# master_jorge3.net
KiCad netlist of a schematic drawn in EAGLE
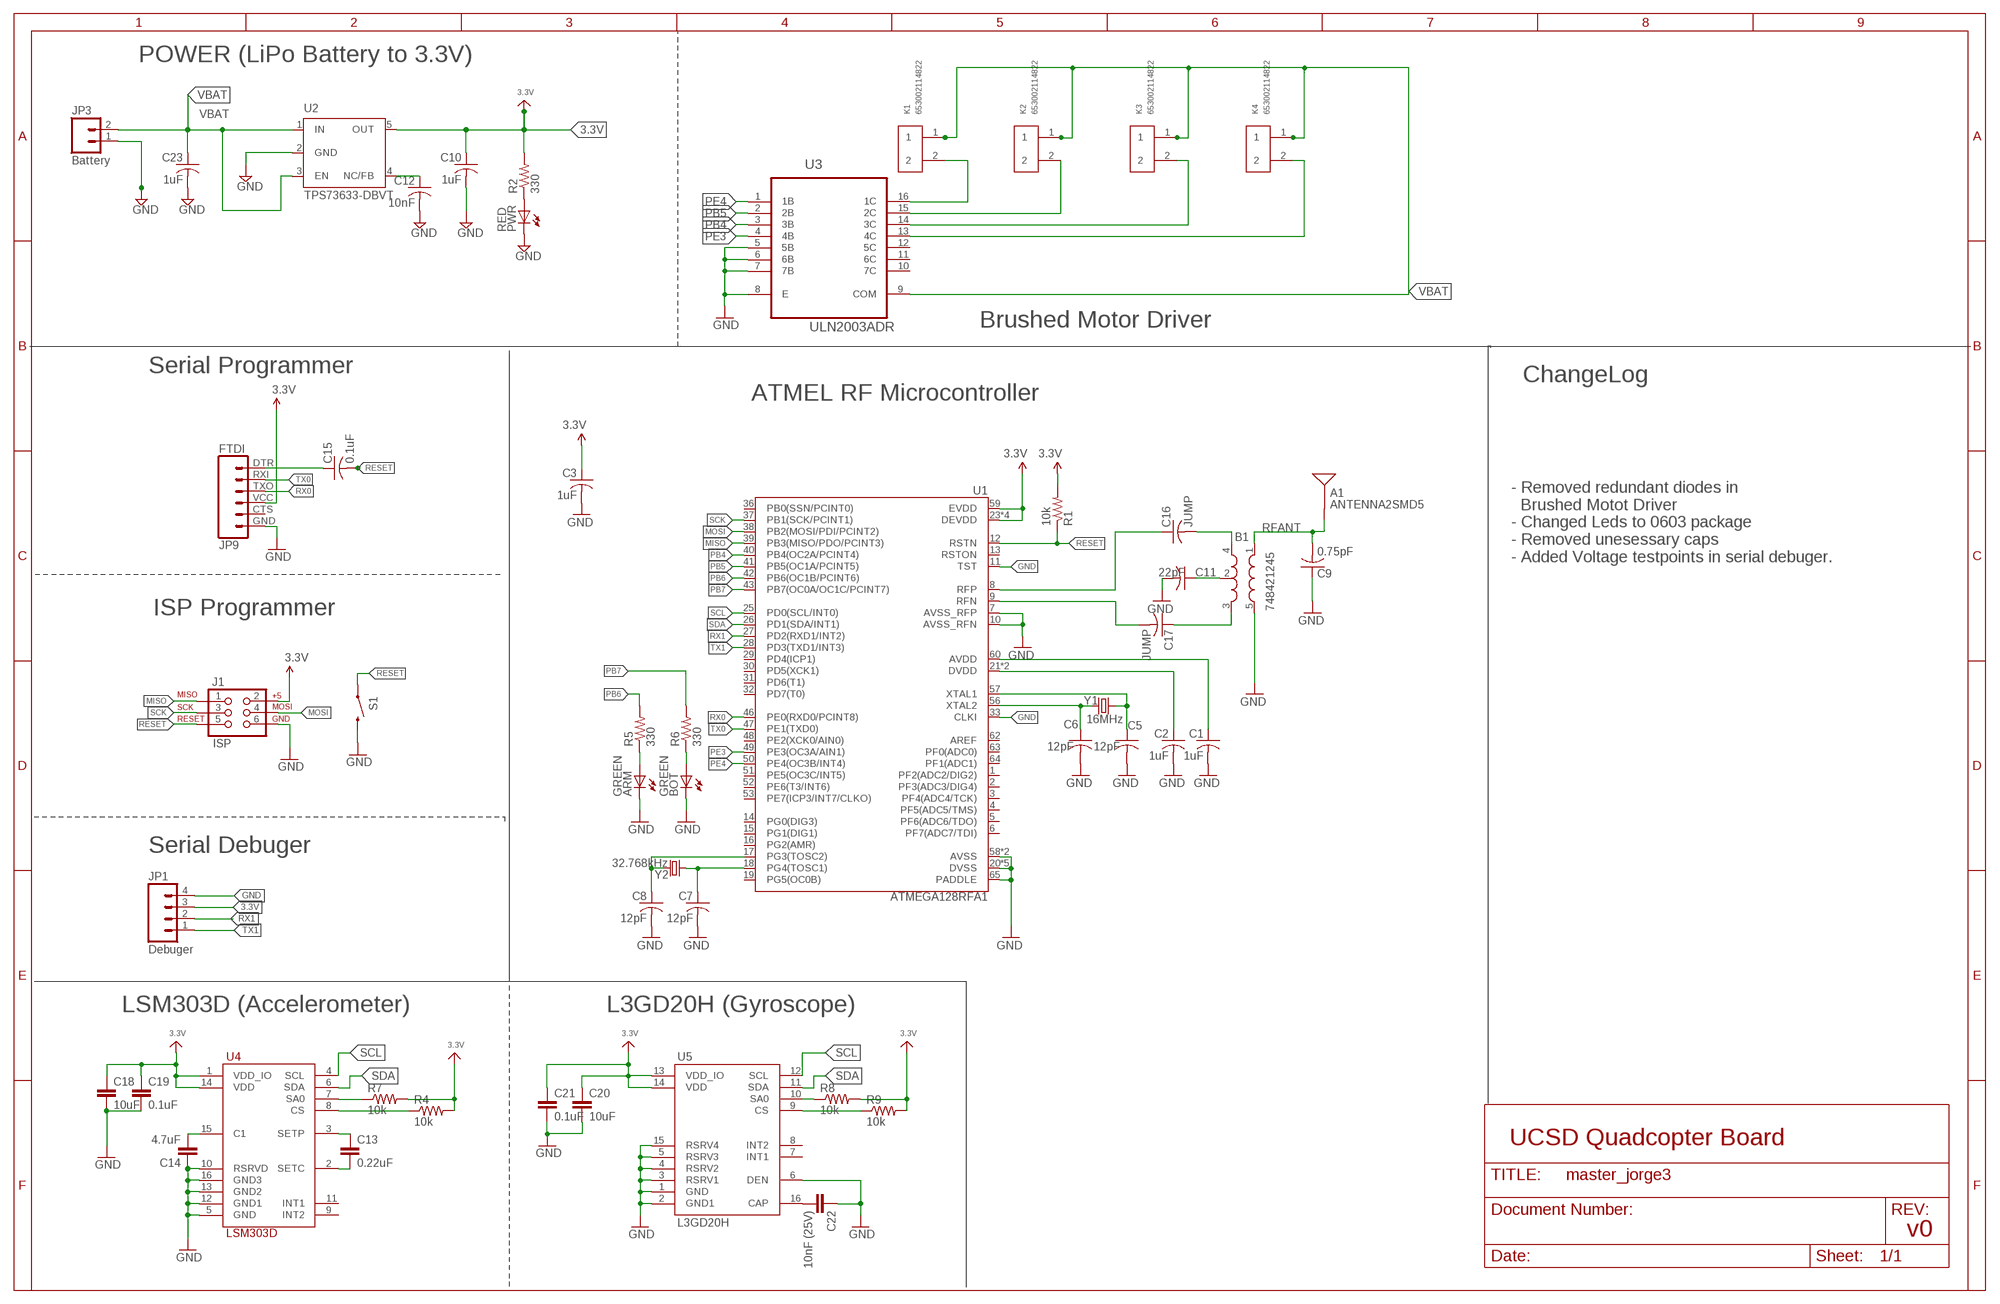
[diagram p0: schematic, sheet 1]

(export (version "E")
  (design (tool "Eeschema 10.0.6"))
  (components
    (comp (ref "A1")
      (value "ANTENNA2SMD5")
      (footprint "eagle-import:ANTENNA-CHIP5")
      (libsource (lib "eagle-import") (part "ANTENNA2SMD5"))
    )
    (comp (ref "ARM")
      (value "GREEN")
      (footprint "eagle-import:CHIPLED_0603")
      (libsource (lib "eagle-import") (part "LEDCHIPLED_0603"))
    )
    (comp (ref "B1")
      (value "748421245")
      (footprint "eagle-import:BALUN")
      (libsource (lib "eagle-import") (part "BALUN0805"))
    )
    (comp (ref "BOT")
      (value "GREEN")
      (footprint "eagle-import:CHIPLED_0603")
      (libsource (lib "eagle-import") (part "LEDCHIPLED_0603"))
    )
    (comp (ref "C1")
      (value "1uF")
      (footprint "eagle-import:C0805")
      (libsource (lib "eagle-import") (part "C-USC0805"))
    )
    (comp (ref "C2")
      (value "1uF")
      (footprint "eagle-import:C0805")
      (libsource (lib "eagle-import") (part "C-USC0805"))
    )
    (comp (ref "C3")
      (value "1uF")
      (footprint "eagle-import:C0805")
      (libsource (lib "eagle-import") (part "C-USC0805"))
    )
    (comp (ref "C5")
      (value "12pF")
      (footprint "eagle-import:C0805")
      (libsource (lib "eagle-import") (part "C-USC0805"))
    )
    (comp (ref "C6")
      (value "12pF")
      (footprint "eagle-import:C0805")
      (libsource (lib "eagle-import") (part "C-USC0805"))
    )
    (comp (ref "C7")
      (value "12pF")
      (footprint "eagle-import:C0805")
      (libsource (lib "eagle-import") (part "C-USC0805"))
    )
    (comp (ref "C8")
      (value "12pF")
      (footprint "eagle-import:C0805")
      (libsource (lib "eagle-import") (part "C-USC0805"))
    )
    (comp (ref "C9")
      (value "0.75pF")
      (footprint "eagle-import:C0805")
      (libsource (lib "eagle-import") (part "C-USC0805"))
    )
    (comp (ref "C10")
      (value "1uF")
      (footprint "eagle-import:C0805")
      (libsource (lib "eagle-import") (part "C-USC0805"))
    )
    (comp (ref "C11")
      (value "22pF")
      (footprint "eagle-import:C0805")
      (libsource (lib "eagle-import") (part "C-USC0805"))
    )
    (comp (ref "C12")
      (value "10nF")
      (footprint "eagle-import:C0805")
      (libsource (lib "eagle-import") (part "C-USC0805"))
    )
    (comp (ref "C13")
      (value "0.22uF")
      (footprint "eagle-import:0805")
      (libsource (lib "eagle-import") (part "CAP0805"))
    )
    (comp (ref "C14")
      (value "4.7uF")
      (footprint "eagle-import:0805")
      (libsource (lib "eagle-import") (part "CAP0805"))
    )
    (comp (ref "C15")
      (value "0.1uF")
      (footprint "eagle-import:C0805")
      (libsource (lib "eagle-import") (part "C-USC0805"))
    )
    (comp (ref "C16")
      (value "JUMP")
      (footprint "eagle-import:C0805")
      (libsource (lib "eagle-import") (part "C-USC0805"))
    )
    (comp (ref "C17")
      (value "JUMP")
      (footprint "eagle-import:C0805")
      (libsource (lib "eagle-import") (part "C-USC0805"))
    )
    (comp (ref "C18")
      (value "10uF")
      (footprint "eagle-import:0805")
      (libsource (lib "eagle-import") (part "CAP0805"))
    )
    (comp (ref "C19")
      (value "0.1uF")
      (footprint "eagle-import:0805")
      (libsource (lib "eagle-import") (part "CAP0805"))
    )
    (comp (ref "C20")
      (value "10uF")
      (footprint "eagle-import:0805")
      (libsource (lib "eagle-import") (part "CAP0805"))
    )
    (comp (ref "C21")
      (value "0.1uF")
      (footprint "eagle-import:0805")
      (libsource (lib "eagle-import") (part "CAP0805"))
    )
    (comp (ref "C22")
      (value "10nF (25V)")
      (footprint "eagle-import:0805")
      (libsource (lib "eagle-import") (part "CAP0805"))
    )
    (comp (ref "C23")
      (value "1uF")
      (footprint "eagle-import:C0805")
      (libsource (lib "eagle-import") (part "C-USC0805"))
    )
    (comp (ref "J1")
      (value "ISP")
      (footprint "eagle-import:2X3-NS")
      (libsource (lib "eagle-import") (part "AVR_SPI_PRG_6NS"))
    )
    (comp (ref "JP1")
      (value "Debuger")
      (footprint "eagle-import:1X04")
      (libsource (lib "eagle-import") (part "M04PTH"))
    )
    (comp (ref "JP3")
      (value "Battery")
      (footprint "eagle-import:1X02")
      (libsource (lib "eagle-import") (part "M02PTH"))
    )
    (comp (ref "JP9")
      (value "FTDI")
      (footprint "eagle-import:FTDI_BASIC")
      (libsource (lib "eagle-import") (part "FTDI_BASICPTH"))
    )
    (comp (ref "K1")
      (value "653002114822")
      (footprint "eagle-import:653002114822")
      (libsource (lib "eagle-import") (part "653002114822"))
    )
    (comp (ref "K2")
      (value "653002114822")
      (footprint "eagle-import:653002114822")
      (libsource (lib "eagle-import") (part "653002114822"))
    )
    (comp (ref "K3")
      (value "653002114822")
      (footprint "eagle-import:653002114822")
      (libsource (lib "eagle-import") (part "653002114822"))
    )
    (comp (ref "K4")
      (value "653002114822")
      (footprint "eagle-import:653002114822")
      (libsource (lib "eagle-import") (part "653002114822"))
    )
    (comp (ref "PWR")
      (value "RED")
      (footprint "eagle-import:CHIPLED_0603")
      (libsource (lib "eagle-import") (part "LEDCHIPLED_0603"))
    )
    (comp (ref "R1")
      (value "10k")
      (footprint "eagle-import:R0805")
      (libsource (lib "eagle-import") (part "R-US_R0805"))
    )
    (comp (ref "R2")
      (value "330")
      (footprint "eagle-import:R0805")
      (libsource (lib "eagle-import") (part "R-US_R0805"))
    )
    (comp (ref "R4")
      (value "10k")
      (footprint "eagle-import:0805")
      (libsource (lib "eagle-import") (part "RESISTOR0805-RES"))
    )
    (comp (ref "R5")
      (value "330")
      (footprint "eagle-import:R0805")
      (libsource (lib "eagle-import") (part "R-US_R0805"))
    )
    (comp (ref "R6")
      (value "330")
      (footprint "eagle-import:R0805")
      (libsource (lib "eagle-import") (part "R-US_R0805"))
    )
    (comp (ref "R7")
      (value "10k")
      (footprint "eagle-import:0805")
      (libsource (lib "eagle-import") (part "RESISTOR0805-RES"))
    )
    (comp (ref "R8")
      (value "10k")
      (footprint "eagle-import:0805")
      (libsource (lib "eagle-import") (part "RESISTOR0805-RES"))
    )
    (comp (ref "R9")
      (value "10k")
      (footprint "eagle-import:0805")
      (libsource (lib "eagle-import") (part "RESISTOR0805-RES"))
    )
    (comp (ref "S1")
      (value "SWITCH-MOMENTARY-2SMD")
      (footprint "eagle-import:TACTILE_SWITCH_SMD")
      (libsource (lib "eagle-import") (part "SWITCH-MOMENTARY-2SMD"))
    )
    (comp (ref "U1")
      (value "ATMEGA128RFA1")
      (footprint "eagle-import:QFN-64")
      (libsource (lib "eagle-import") (part "ATMEGA128RFA1"))
    )
    (comp (ref "U2")
      (value "TPS73633-DBVT")
      (footprint "eagle-import:SOT23-DBV")
      (libsource (lib "eagle-import") (part "TPS73633-DBVT"))
    )
    (comp (ref "U3")
      (value "ULN2003ADR")
      (footprint "eagle-import:SOIC127P600X175-16N")
      (libsource (lib "eagle-import") (part "ULN2003ADR"))
    )
    (comp (ref "U4")
      (value "LSM303D")
      (footprint "eagle-import:LGA16_3X3MM")
      (libsource (lib "eagle-import") (part "LSM303D"))
    )
    (comp (ref "U5")
      (value "L3GD20H")
      (footprint "eagle-import:LGA16_3X3MM")
      (libsource (lib "eagle-import") (part "L3GD20H"))
    )
    (comp (ref "Y1")
      (value "16MHz")
      (footprint "eagle-import:CRYSTAL-SMD-5X3")
      (libsource (lib "eagle-import") (part "CRYSTAL5X3"))
    )
    (comp (ref "Y2")
      (value "32.768kHz")
      (footprint "eagle-import:CRYSTAL-32KHZ-SMD")
      (libsource (lib "eagle-import") (part "CRYSTAL32-SMD"))
    )
  )
  (nets
    (net (code "1") (name "/RFANT") (class "Default")
      (node (ref "A1") (pin "FEED") (pinfunction "SIGNAL_FEED") (pintype "bidirectional"))
      (node (ref "B1") (pin "1") (pinfunction "IN_1") (pintype "bidirectional"))
      (node (ref "C9") (pin "2") (pinfunction "2_2") (pintype "passive"))
    )
    (net (code "2") (name "3.3V") (class "Default")
      (node (ref "C10") (pin "1") (pinfunction "1_1") (pintype "passive"))
      (node (ref "C18") (pin "1") (pinfunction "1_1") (pintype "passive"))
      (node (ref "C19") (pin "1") (pinfunction "1_1") (pintype "passive"))
      (node (ref "C20") (pin "1") (pinfunction "1_1") (pintype "passive"))
      (node (ref "C21") (pin "1") (pinfunction "1_1") (pintype "passive"))
      (node (ref "C3") (pin "1") (pinfunction "1_1") (pintype "passive"))
      (node (ref "J1") (pin "2") (pinfunction "2_2") (pintype "passive"))
      (node (ref "JP1") (pin "3") (pinfunction "3_3") (pintype "passive"))
      (node (ref "JP9") (pin "VCC") (pinfunction "4_VCC") (pintype "passive"))
      (node (ref "R1") (pin "2") (pinfunction "2_2") (pintype "passive"))
      (node (ref "R2") (pin "2") (pinfunction "2_2") (pintype "passive"))
      (node (ref "R4") (pin "2") (pinfunction "2_2") (pintype "passive"))
      (node (ref "R7") (pin "2") (pinfunction "2_2") (pintype "passive"))
      (node (ref "R8") (pin "2") (pinfunction "2_2") (pintype "passive"))
      (node (ref "R9") (pin "2") (pinfunction "2_2") (pintype "passive"))
      (node (ref "U1") (pin "23") (pinfunction "DEVDD_23") (pintype "bidirectional"))
      (node (ref "U1") (pin "34") (pinfunction "DEVDD_34") (pintype "bidirectional"))
      (node (ref "U1") (pin "44") (pinfunction "DEVDD_44") (pintype "bidirectional"))
      (node (ref "U1") (pin "54") (pinfunction "DEVDD_54") (pintype "bidirectional"))
      (node (ref "U1") (pin "59") (pinfunction "EVDD_59") (pintype "bidirectional"))
      (node (ref "U2") (pin "5") (pinfunction "OUT_5") (pintype "passive"))
      (node (ref "U4") (pin "1") (pinfunction "VDD_IO_1") (pintype "bidirectional"))
      (node (ref "U4") (pin "14") (pinfunction "VDD_14") (pintype "bidirectional"))
      (node (ref "U5") (pin "13") (pinfunction "VDD_IO_13") (pintype "bidirectional"))
      (node (ref "U5") (pin "14") (pinfunction "VDD_14") (pintype "bidirectional"))
    )
    (net (code "3") (name "GND") (class "Default")
      (node (ref "ARM") (pin "C") (pinfunction "C_C") (pintype "passive"))
      (node (ref "B1") (pin "5") (pinfunction "GND_5") (pintype "bidirectional"))
      (node (ref "BOT") (pin "C") (pinfunction "C_C") (pintype "passive"))
      (node (ref "C1") (pin "2") (pinfunction "2_2") (pintype "passive"))
      (node (ref "C10") (pin "2") (pinfunction "2_2") (pintype "passive"))
      (node (ref "C11") (pin "2") (pinfunction "2_2") (pintype "passive"))
      (node (ref "C12") (pin "2") (pinfunction "2_2") (pintype "passive"))
      (node (ref "C14") (pin "1") (pinfunction "1_1") (pintype "passive"))
      (node (ref "C18") (pin "2") (pinfunction "2_2") (pintype "passive"))
      (node (ref "C19") (pin "2") (pinfunction "2_2") (pintype "passive"))
      (node (ref "C2") (pin "2") (pinfunction "2_2") (pintype "passive"))
      (node (ref "C20") (pin "2") (pinfunction "2_2") (pintype "passive"))
      (node (ref "C21") (pin "2") (pinfunction "2_2") (pintype "passive"))
      (node (ref "C22") (pin "1") (pinfunction "1_1") (pintype "passive"))
      (node (ref "C23") (pin "2") (pinfunction "2_2") (pintype "passive"))
      (node (ref "C3") (pin "2") (pinfunction "2_2") (pintype "passive"))
      (node (ref "C5") (pin "2") (pinfunction "2_2") (pintype "passive"))
      (node (ref "C6") (pin "2") (pinfunction "2_2") (pintype "passive"))
      (node (ref "C7") (pin "2") (pinfunction "2_2") (pintype "passive"))
      (node (ref "C8") (pin "2") (pinfunction "2_2") (pintype "passive"))
      (node (ref "C9") (pin "1") (pinfunction "1_1") (pintype "passive"))
      (node (ref "J1") (pin "6") (pinfunction "6_6") (pintype "passive"))
      (node (ref "JP1") (pin "4") (pinfunction "4_4") (pintype "passive"))
      (node (ref "JP3") (pin "1") (pinfunction "1_1") (pintype "passive"))
      (node (ref "JP9") (pin "GND") (pinfunction "6_GND") (pintype "passive"))
      (node (ref "PWR") (pin "C") (pinfunction "C_C") (pintype "passive"))
      (node (ref "S1") (pin "3") (pinfunction "2_3") (pintype "passive"))
      (node (ref "U1") (pin "10") (pinfunction "AVSS_RFN_10") (pintype "bidirectional"))
      (node (ref "U1") (pin "11") (pinfunction "TST_11") (pintype "bidirectional"))
      (node (ref "U1") (pin "20") (pinfunction "DVSS_20") (pintype "bidirectional"))
      (node (ref "U1") (pin "24") (pinfunction "DVSS_24") (pintype "bidirectional"))
      (node (ref "U1") (pin "33") (pinfunction "CLKI_33") (pintype "bidirectional"))
      (node (ref "U1") (pin "35") (pinfunction "DVSS_35") (pintype "bidirectional"))
      (node (ref "U1") (pin "45") (pinfunction "DVSS_45") (pintype "bidirectional"))
      (node (ref "U1") (pin "55") (pinfunction "DVSS_55") (pintype "bidirectional"))
      (node (ref "U1") (pin "58") (pinfunction "AVSS_58") (pintype "bidirectional"))
      (node (ref "U1") (pin "61") (pinfunction "AVSS_61") (pintype "bidirectional"))
      (node (ref "U1") (pin "65") (pinfunction "PADDLE_65") (pintype "bidirectional"))
      (node (ref "U1") (pin "7") (pinfunction "AVSS_RFP_7") (pintype "bidirectional"))
      (node (ref "U2") (pin "2") (pinfunction "GND_2") (pintype "input"))
      (node (ref "U3") (pin "5") (pinfunction "5B_5") (pintype "input"))
      (node (ref "U3") (pin "6") (pinfunction "6B_6") (pintype "input"))
      (node (ref "U3") (pin "7") (pinfunction "7B_7") (pintype "input"))
      (node (ref "U3") (pin "8") (pinfunction "E_8") (pintype "input"))
      (node (ref "U4") (pin "10") (pinfunction "RSRVD_10") (pintype "bidirectional"))
      (node (ref "U4") (pin "12") (pinfunction "GND1_12") (pintype "bidirectional"))
      (node (ref "U4") (pin "13") (pinfunction "GND2_13") (pintype "bidirectional"))
      (node (ref "U4") (pin "16") (pinfunction "GND3_16") (pintype "bidirectional"))
      (node (ref "U4") (pin "5") (pinfunction "GND_5") (pintype "bidirectional"))
      (node (ref "U5") (pin "1") (pinfunction "GND_1") (pintype "bidirectional"))
      (node (ref "U5") (pin "15") (pinfunction "RSRV4_15") (pintype "bidirectional"))
      (node (ref "U5") (pin "2") (pinfunction "GND1_2") (pintype "bidirectional"))
      (node (ref "U5") (pin "3") (pinfunction "RSRV1_3") (pintype "bidirectional"))
      (node (ref "U5") (pin "4") (pinfunction "RSRV2_4") (pintype "bidirectional"))
      (node (ref "U5") (pin "5") (pinfunction "RSRV3_5") (pintype "bidirectional"))
      (node (ref "U5") (pin "6") (pinfunction "DEN_6") (pintype "bidirectional"))
    )
    (net (code "4") (name "MISO") (class "Default")
      (node (ref "J1") (pin "1") (pinfunction "1_1") (pintype "passive"))
      (node (ref "U1") (pin "39") (pinfunction "PB3(MISO/PDO/PCINT3)_39") (pintype "bidirectional"))
    )
    (net (code "5") (name "MOSI") (class "Default")
      (node (ref "J1") (pin "4") (pinfunction "4_4") (pintype "passive"))
      (node (ref "U1") (pin "38") (pinfunction "PB2(MOSI/PDI/PCINT2)_38") (pintype "bidirectional"))
    )
    (net (code "6") (name "Net-(ARM-PadA)") (class "Default")
      (node (ref "ARM") (pin "A") (pinfunction "A_A") (pintype "passive"))
      (node (ref "R5") (pin "1") (pinfunction "1_1") (pintype "passive"))
    )
    (net (code "7") (name "Net-(B1-GND-Pad2)") (class "Default")
      (node (ref "B1") (pin "2") (pinfunction "GND_2") (pintype "bidirectional"))
      (node (ref "C11") (pin "1") (pinfunction "1_1") (pintype "passive"))
    )
    (net (code "8") (name "Net-(B1-OUT1)") (class "Default")
      (node (ref "B1") (pin "4") (pinfunction "OUT1_4") (pintype "bidirectional"))
      (node (ref "C16") (pin "2") (pinfunction "2_2") (pintype "passive"))
    )
    (net (code "9") (name "Net-(B1-OUT2)") (class "Default")
      (node (ref "B1") (pin "3") (pinfunction "OUT2_3") (pintype "bidirectional"))
      (node (ref "C17") (pin "1") (pinfunction "1_1") (pintype "passive"))
    )
    (net (code "10") (name "Net-(BOT-PadA)") (class "Default")
      (node (ref "BOT") (pin "A") (pinfunction "A_A") (pintype "passive"))
      (node (ref "R6") (pin "1") (pinfunction "1_1") (pintype "passive"))
    )
    (net (code "11") (name "Net-(C2-Pad1)") (class "Default")
      (node (ref "C2") (pin "1") (pinfunction "1_1") (pintype "passive"))
      (node (ref "U1") (pin "21") (pinfunction "DVDD_21") (pintype "bidirectional"))
      (node (ref "U1") (pin "22") (pinfunction "DVDD_22") (pintype "bidirectional"))
    )
    (net (code "12") (name "Net-(JP9-1)") (class "Default")
      (node (ref "C15") (pin "1") (pinfunction "1_1") (pintype "passive"))
      (node (ref "JP9") (pin "DTR") (pinfunction "1_DTR") (pintype "passive"))
    )
    (net (code "13") (name "Net-(PWR-PadA)") (class "Default")
      (node (ref "PWR") (pin "A") (pinfunction "A_A") (pintype "passive"))
      (node (ref "R2") (pin "1") (pinfunction "1_1") (pintype "passive"))
    )
    (net (code "14") (name "Net-(U1-AVDD)") (class "Default")
      (node (ref "C1") (pin "1") (pinfunction "1_1") (pintype "passive"))
      (node (ref "U1") (pin "60") (pinfunction "AVDD_60") (pintype "bidirectional"))
    )
    (net (code "15") (name "Net-(U1-PG3(TOSC2))") (class "Default")
      (node (ref "C8") (pin "1") (pinfunction "1_1") (pintype "passive"))
      (node (ref "U1") (pin "17") (pinfunction "PG3(TOSC2)_17") (pintype "bidirectional"))
      (node (ref "Y2") (pin "X2") (pinfunction "2_X2") (pintype "passive"))
    )
    (net (code "16") (name "Net-(U1-PG4(TOSC1))") (class "Default")
      (node (ref "C7") (pin "1") (pinfunction "1_1") (pintype "passive"))
      (node (ref "U1") (pin "18") (pinfunction "PG4(TOSC1)_18") (pintype "bidirectional"))
      (node (ref "Y2") (pin "X1") (pinfunction "1_X1") (pintype "passive"))
    )
    (net (code "17") (name "Net-(U1-RFN)") (class "Default")
      (node (ref "C17") (pin "2") (pinfunction "2_2") (pintype "passive"))
      (node (ref "U1") (pin "9") (pinfunction "RFN_9") (pintype "bidirectional"))
    )
    (net (code "18") (name "Net-(U1-RFP)") (class "Default")
      (node (ref "C16") (pin "1") (pinfunction "1_1") (pintype "passive"))
      (node (ref "U1") (pin "8") (pinfunction "RFP_8") (pintype "bidirectional"))
    )
    (net (code "19") (name "Net-(U1-XTAL1)") (class "Default")
      (node (ref "C5") (pin "1") (pinfunction "1_1") (pintype "passive"))
      (node (ref "U1") (pin "57") (pinfunction "XTAL1_57") (pintype "bidirectional"))
      (node (ref "Y1") (pin "3") (pinfunction "2_3") (pintype "passive"))
    )
    (net (code "20") (name "Net-(U1-XTAL2)") (class "Default")
      (node (ref "C6") (pin "1") (pinfunction "1_1") (pintype "passive"))
      (node (ref "U1") (pin "56") (pinfunction "XTAL2_56") (pintype "bidirectional"))
      (node (ref "Y1") (pin "1") (pinfunction "1_1") (pintype "passive"))
    )
    (net (code "21") (name "Net-(U2-NC{slash}FB)") (class "Default")
      (node (ref "C12") (pin "1") (pinfunction "1_1") (pintype "passive"))
      (node (ref "U2") (pin "4") (pinfunction "NC/FB_4") (pintype "passive"))
    )
    (net (code "22") (name "Net-(U3-1C)") (class "Default")
      (node (ref "K1") (pin "2") (pinfunction "2_2") (pintype "bidirectional"))
      (node (ref "U3") (pin "16") (pinfunction "1C_16") (pintype "output"))
    )
    (net (code "23") (name "Net-(U3-2C)") (class "Default")
      (node (ref "K2") (pin "2") (pinfunction "2_2") (pintype "bidirectional"))
      (node (ref "U3") (pin "15") (pinfunction "2C_15") (pintype "output"))
    )
    (net (code "24") (name "Net-(U3-3C)") (class "Default")
      (node (ref "K3") (pin "2") (pinfunction "2_2") (pintype "bidirectional"))
      (node (ref "U3") (pin "14") (pinfunction "3C_14") (pintype "output"))
    )
    (net (code "25") (name "Net-(U3-4C)") (class "Default")
      (node (ref "K4") (pin "2") (pinfunction "2_2") (pintype "bidirectional"))
      (node (ref "U3") (pin "13") (pinfunction "4C_13") (pintype "output"))
    )
    (net (code "26") (name "Net-(U4-C1)") (class "Default")
      (node (ref "C14") (pin "2") (pinfunction "2_2") (pintype "passive"))
      (node (ref "U4") (pin "15") (pinfunction "C1_15") (pintype "bidirectional"))
    )
    (net (code "27") (name "Net-(U4-CS)") (class "Default")
      (node (ref "R4") (pin "1") (pinfunction "1_1") (pintype "passive"))
      (node (ref "U4") (pin "8") (pinfunction "CS_8") (pintype "bidirectional"))
    )
    (net (code "28") (name "Net-(U4-SA0)") (class "Default")
      (node (ref "R7") (pin "1") (pinfunction "1_1") (pintype "passive"))
      (node (ref "U4") (pin "7") (pinfunction "SA0_7") (pintype "bidirectional"))
    )
    (net (code "29") (name "Net-(U4-SETC)") (class "Default")
      (node (ref "C13") (pin "2") (pinfunction "2_2") (pintype "passive"))
      (node (ref "U4") (pin "2") (pinfunction "SETC_2") (pintype "bidirectional"))
    )
    (net (code "30") (name "Net-(U4-SETP)") (class "Default")
      (node (ref "C13") (pin "1") (pinfunction "1_1") (pintype "passive"))
      (node (ref "U4") (pin "3") (pinfunction "SETP_3") (pintype "bidirectional"))
    )
    (net (code "31") (name "Net-(U5-CAP)") (class "Default")
      (node (ref "C22") (pin "2") (pinfunction "2_2") (pintype "passive"))
      (node (ref "U5") (pin "16") (pinfunction "CAP_16") (pintype "bidirectional"))
    )
    (net (code "32") (name "Net-(U5-CS)") (class "Default")
      (node (ref "R9") (pin "1") (pinfunction "1_1") (pintype "passive"))
      (node (ref "U5") (pin "9") (pinfunction "CS_9") (pintype "bidirectional"))
    )
    (net (code "33") (name "Net-(U5-SA0)") (class "Default")
      (node (ref "R8") (pin "1") (pinfunction "1_1") (pintype "passive"))
      (node (ref "U5") (pin "10") (pinfunction "SA0_10") (pintype "bidirectional"))
    )
    (net (code "34") (name "PB4") (class "Default")
      (node (ref "U1") (pin "40") (pinfunction "PB4(OC2A/PCINT4)_40") (pintype "bidirectional"))
      (node (ref "U3") (pin "3") (pinfunction "3B_3") (pintype "input"))
    )
    (net (code "35") (name "PB5") (class "Default")
      (node (ref "U1") (pin "41") (pinfunction "PB5(OC1A/PCINT5)_41") (pintype "bidirectional"))
      (node (ref "U3") (pin "2") (pinfunction "2B_2") (pintype "input"))
    )
    (net (code "36") (name "PB6") (class "Default")
      (node (ref "R5") (pin "2") (pinfunction "2_2") (pintype "passive"))
      (node (ref "U1") (pin "42") (pinfunction "PB6(OC1B/PCINT6)_42") (pintype "bidirectional"))
    )
    (net (code "37") (name "PB7") (class "Default")
      (node (ref "R6") (pin "2") (pinfunction "2_2") (pintype "passive"))
      (node (ref "U1") (pin "43") (pinfunction "PB7(OC0A/OC1C/PCINT7)_43") (pintype "bidirectional"))
    )
    (net (code "38") (name "PE3") (class "Default")
      (node (ref "U1") (pin "49") (pinfunction "PE3(OC3A/AIN1)_49") (pintype "bidirectional"))
      (node (ref "U3") (pin "4") (pinfunction "4B_4") (pintype "input"))
    )
    (net (code "39") (name "PE4") (class "Default")
      (node (ref "U1") (pin "50") (pinfunction "PE4(OC3B/INT4)_50") (pintype "bidirectional"))
      (node (ref "U3") (pin "1") (pinfunction "1B_1") (pintype "input"))
    )
    (net (code "40") (name "RESET") (class "Default")
      (node (ref "C15") (pin "2") (pinfunction "2_2") (pintype "passive"))
      (node (ref "J1") (pin "5") (pinfunction "5_5") (pintype "passive"))
      (node (ref "R1") (pin "1") (pinfunction "1_1") (pintype "passive"))
      (node (ref "S1") (pin "1") (pinfunction "1_1") (pintype "passive"))
      (node (ref "U1") (pin "12") (pinfunction "RSTN_12") (pintype "bidirectional"))
    )
    (net (code "41") (name "RX0") (class "Default")
      (node (ref "JP9") (pin "TXO") (pinfunction "3_TXO") (pintype "passive"))
      (node (ref "U1") (pin "46") (pinfunction "PE0(RXD0/PCINT8)_46") (pintype "bidirectional"))
    )
    (net (code "42") (name "RX1") (class "Default")
      (node (ref "JP1") (pin "2") (pinfunction "2_2") (pintype "passive"))
      (node (ref "U1") (pin "27") (pinfunction "PD2(RXD1/INT2)_27") (pintype "bidirectional"))
    )
    (net (code "43") (name "SCK") (class "Default")
      (node (ref "J1") (pin "3") (pinfunction "3_3") (pintype "passive"))
      (node (ref "U1") (pin "37") (pinfunction "PB1(SCK/PCINT1)_37") (pintype "bidirectional"))
    )
    (net (code "44") (name "SCL") (class "Default")
      (node (ref "U1") (pin "25") (pinfunction "PD0(SCL/INT0)_25") (pintype "bidirectional"))
      (node (ref "U4") (pin "4") (pinfunction "SCL_4") (pintype "bidirectional"))
      (node (ref "U5") (pin "12") (pinfunction "SCL_12") (pintype "bidirectional"))
    )
    (net (code "45") (name "SDA") (class "Default")
      (node (ref "U1") (pin "26") (pinfunction "PD1(SDA/INT1)_26") (pintype "bidirectional"))
      (node (ref "U4") (pin "6") (pinfunction "SDA_6") (pintype "bidirectional"))
      (node (ref "U5") (pin "11") (pinfunction "SDA_11") (pintype "bidirectional"))
    )
    (net (code "46") (name "TX0") (class "Default")
      (node (ref "JP9") (pin "RXI") (pinfunction "2_RXI") (pintype "passive"))
      (node (ref "U1") (pin "47") (pinfunction "PE1(TXD0)_47") (pintype "bidirectional"))
    )
    (net (code "47") (name "TX1") (class "Default")
      (node (ref "JP1") (pin "1") (pinfunction "1_1") (pintype "passive"))
      (node (ref "U1") (pin "28") (pinfunction "PD3(TXD1/INT3)_28") (pintype "bidirectional"))
    )
    (net (code "48") (name "VBAT") (class "Default")
      (node (ref "C23") (pin "1") (pinfunction "1_1") (pintype "passive"))
      (node (ref "JP3") (pin "2") (pinfunction "2_2") (pintype "passive"))
      (node (ref "K1") (pin "1") (pinfunction "1_1") (pintype "bidirectional"))
      (node (ref "K2") (pin "1") (pinfunction "1_1") (pintype "bidirectional"))
      (node (ref "K3") (pin "1") (pinfunction "1_1") (pintype "bidirectional"))
      (node (ref "K4") (pin "1") (pinfunction "1_1") (pintype "bidirectional"))
      (node (ref "U2") (pin "1") (pinfunction "IN_1") (pintype "input"))
      (node (ref "U2") (pin "3") (pinfunction "EN_3") (pintype "power_in"))
      (node (ref "U3") (pin "9") (pinfunction "COM_9") (pintype "output"))
    )
    (net (code "49") (name "unconnected-(JP9-5-PadCTS)") (class "Default")
      (node (ref "JP9") (pin "CTS") (pinfunction "5_CTS") (pintype "passive"))
    )
    (net (code "50") (name "unconnected-(U1-AREF-Pad62)") (class "Default")
      (node (ref "U1") (pin "62") (pinfunction "AREF_62") (pintype "bidirectional"))
    )
    (net (code "51") (name "unconnected-(U1-PB0(SSN{slash}PCINT0)-Pad36)") (class "Default")
      (node (ref "U1") (pin "36") (pinfunction "PB0(SSN/PCINT0)_36") (pintype "bidirectional"))
    )
    (net (code "52") (name "unconnected-(U1-PD4(ICP1)-Pad29)") (class "Default")
      (node (ref "U1") (pin "29") (pinfunction "PD4(ICP1)_29") (pintype "bidirectional"))
    )
    (net (code "53") (name "unconnected-(U1-PD5(XCK1)-Pad30)") (class "Default")
      (node (ref "U1") (pin "30") (pinfunction "PD5(XCK1)_30") (pintype "bidirectional"))
    )
    (net (code "54") (name "unconnected-(U1-PD6(T1)-Pad31)") (class "Default")
      (node (ref "U1") (pin "31") (pinfunction "PD6(T1)_31") (pintype "bidirectional"))
    )
    (net (code "55") (name "unconnected-(U1-PD7(T0)-Pad32)") (class "Default")
      (node (ref "U1") (pin "32") (pinfunction "PD7(T0)_32") (pintype "bidirectional"))
    )
    (net (code "56") (name "unconnected-(U1-PE2(XCK0{slash}AIN0)-Pad48)") (class "Default")
      (node (ref "U1") (pin "48") (pinfunction "PE2(XCK0/AIN0)_48") (pintype "bidirectional"))
    )
    (net (code "57") (name "unconnected-(U1-PE5(OC3C{slash}INT5)-Pad51)") (class "Default")
      (node (ref "U1") (pin "51") (pinfunction "PE5(OC3C/INT5)_51") (pintype "bidirectional"))
    )
    (net (code "58") (name "unconnected-(U1-PE6(T3{slash}INT6)-Pad52)") (class "Default")
      (node (ref "U1") (pin "52") (pinfunction "PE6(T3/INT6)_52") (pintype "bidirectional"))
    )
    (net (code "59") (name "unconnected-(U1-PE7(ICP3{slash}INT7{slash}CLKO)-Pad53)") (class "Default")
      (node (ref "U1") (pin "53") (pinfunction "PE7(ICP3/INT7/CLKO)_53") (pintype "bidirectional"))
    )
    (net (code "60") (name "unconnected-(U1-PF0(ADC0)-Pad63)") (class "Default")
      (node (ref "U1") (pin "63") (pinfunction "PF0(ADC0)_63") (pintype "bidirectional"))
    )
    (net (code "61") (name "unconnected-(U1-PF1(ADC1)-Pad64)") (class "Default")
      (node (ref "U1") (pin "64") (pinfunction "PF1(ADC1)_64") (pintype "bidirectional"))
    )
    (net (code "62") (name "unconnected-(U1-PF2(ADC2{slash}DIG2)-Pad1)") (class "Default")
      (node (ref "U1") (pin "1") (pinfunction "PF2(ADC2/DIG2)_1") (pintype "bidirectional"))
    )
    (net (code "63") (name "unconnected-(U1-PF3(ADC3{slash}DIG4)-Pad2)") (class "Default")
      (node (ref "U1") (pin "2") (pinfunction "PF3(ADC3/DIG4)_2") (pintype "bidirectional"))
    )
    (net (code "64") (name "unconnected-(U1-PF4(ADC4{slash}TCK)-Pad3)") (class "Default")
      (node (ref "U1") (pin "3") (pinfunction "PF4(ADC4/TCK)_3") (pintype "bidirectional"))
    )
    (net (code "65") (name "unconnected-(U1-PF5(ADC5{slash}TMS)-Pad4)") (class "Default")
      (node (ref "U1") (pin "4") (pinfunction "PF5(ADC5/TMS)_4") (pintype "bidirectional"))
    )
    (net (code "66") (name "unconnected-(U1-PF6(ADC6{slash}TDO)-Pad5)") (class "Default")
      (node (ref "U1") (pin "5") (pinfunction "PF6(ADC6/TDO)_5") (pintype "bidirectional"))
    )
    (net (code "67") (name "unconnected-(U1-PF7(ADC7{slash}TDI)-Pad6)") (class "Default")
      (node (ref "U1") (pin "6") (pinfunction "PF7(ADC7/TDI)_6") (pintype "bidirectional"))
    )
    (net (code "68") (name "unconnected-(U1-PG0(DIG3)-Pad14)") (class "Default")
      (node (ref "U1") (pin "14") (pinfunction "PG0(DIG3)_14") (pintype "bidirectional"))
    )
    (net (code "69") (name "unconnected-(U1-PG1(DIG1)-Pad15)") (class "Default")
      (node (ref "U1") (pin "15") (pinfunction "PG1(DIG1)_15") (pintype "bidirectional"))
    )
    (net (code "70") (name "unconnected-(U1-PG2(AMR)-Pad16)") (class "Default")
      (node (ref "U1") (pin "16") (pinfunction "PG2(AMR)_16") (pintype "bidirectional"))
    )
    (net (code "71") (name "unconnected-(U1-PG5(OC0B)-Pad19)") (class "Default")
      (node (ref "U1") (pin "19") (pinfunction "PG5(OC0B)_19") (pintype "bidirectional"))
    )
    (net (code "72") (name "unconnected-(U1-RSTON-Pad13)") (class "Default")
      (node (ref "U1") (pin "13") (pinfunction "RSTON_13") (pintype "bidirectional"))
    )
    (net (code "73") (name "unconnected-(U3-5C-Pad12)") (class "Default")
      (node (ref "U3") (pin "12") (pinfunction "5C_12") (pintype "output"))
    )
    (net (code "74") (name "unconnected-(U3-6C-Pad11)") (class "Default")
      (node (ref "U3") (pin "11") (pinfunction "6C_11") (pintype "output"))
    )
    (net (code "75") (name "unconnected-(U3-7C-Pad10)") (class "Default")
      (node (ref "U3") (pin "10") (pinfunction "7C_10") (pintype "output"))
    )
    (net (code "76") (name "unconnected-(U4-INT1-Pad11)") (class "Default")
      (node (ref "U4") (pin "11") (pinfunction "INT1_11") (pintype "bidirectional"))
    )
    (net (code "77") (name "unconnected-(U4-INT2-Pad9)") (class "Default")
      (node (ref "U4") (pin "9") (pinfunction "INT2_9") (pintype "bidirectional"))
    )
    (net (code "78") (name "unconnected-(U5-INT1-Pad7)") (class "Default")
      (node (ref "U5") (pin "7") (pinfunction "INT1_7") (pintype "bidirectional"))
    )
    (net (code "79") (name "unconnected-(U5-INT2-Pad8)") (class "Default")
      (node (ref "U5") (pin "8") (pinfunction "INT2_8") (pintype "bidirectional"))
    )
  )
)
